# clock10.net
KiCad netlist of a schematic drawn in EAGLE
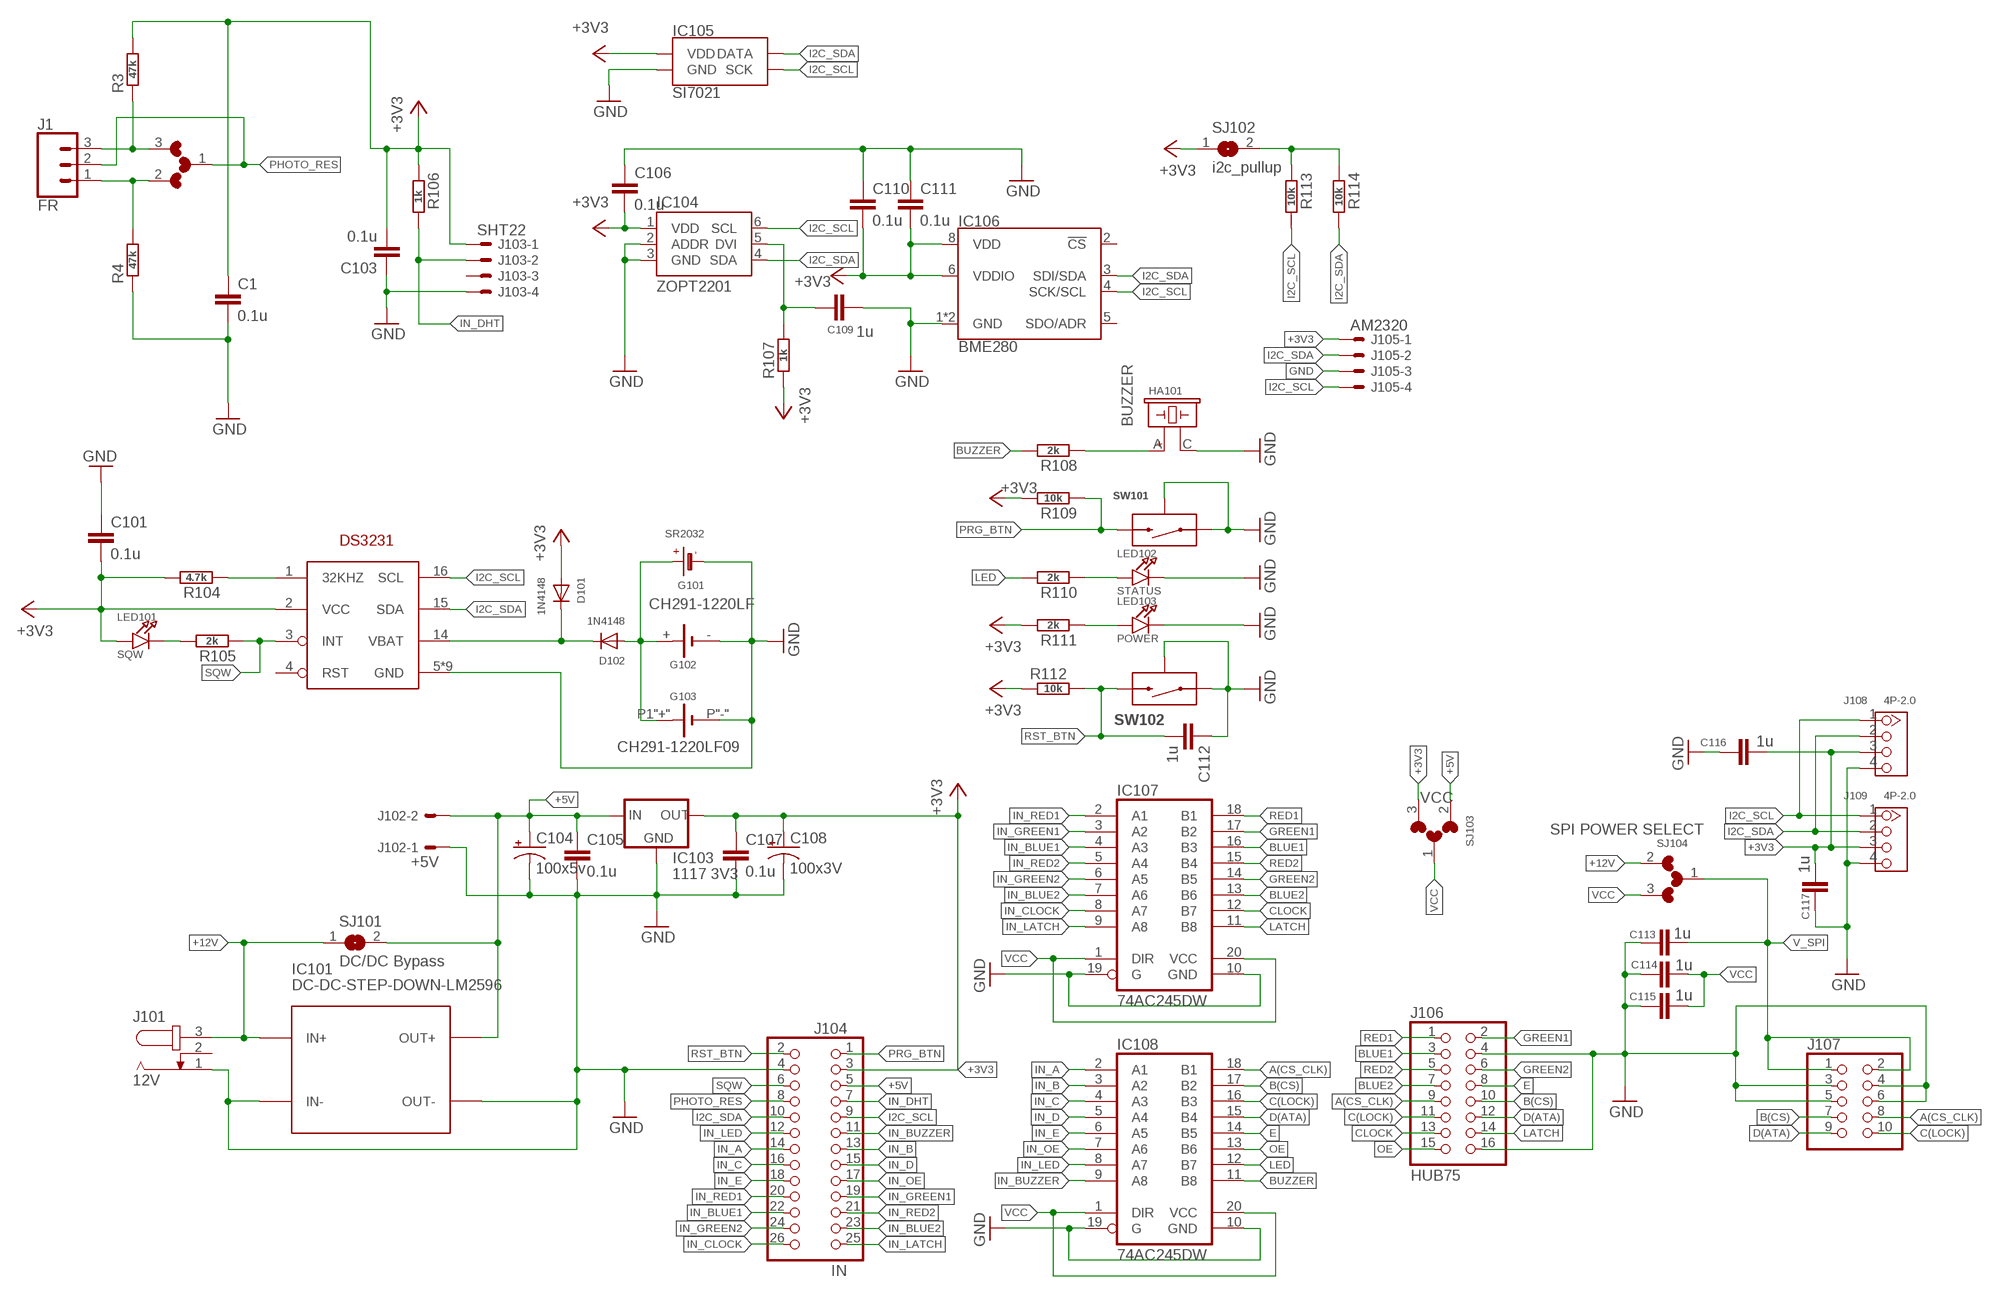
[diagram p0: schematic, sheet 1]
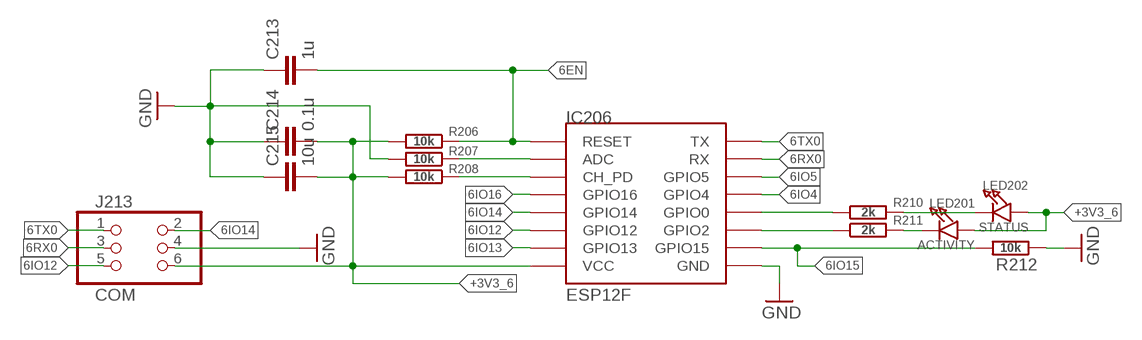
[diagram p1: schematic, sheet 2]

(export (version "E")
  (design (tool "Eeschema 10.0.6"))
  (components
    (comp (ref "C213")
      (value "1u")
      (footprint "eagle-import:0603-CAP")
      (libsource (lib "eagle-import") (part "CAP0603-CAP"))
    )
    (comp (ref "C214")
      (value "0.1u")
      (footprint "eagle-import:0603-CAP")
      (libsource (lib "eagle-import") (part "CAP0603-CAP"))
    )
    (comp (ref "C215")
      (value "10u")
      (footprint "eagle-import:0603-CAP")
      (libsource (lib "eagle-import") (part "CAP0603-CAP"))
    )
    (comp (ref "IC206")
      (value "ESP12F")
      (footprint "eagle-import:ESP12-SMD")
      (libsource (lib "eagle-import") (part "ESP12SMD"))
    )
    (comp (ref "J213")
      (value "COM")
      (footprint "eagle-import:2X03_SMT")
      (libsource (lib "eagle-import") (part "HEADER-2X3SMT"))
    )
    (comp (ref "LED201")
      (value "ACTIVITY")
      (footprint "eagle-import:CHIPLED_0603")
      (libsource (lib "eagle-import") (part "LED0603"))
    )
    (comp (ref "LED202")
      (value "STATUS")
      (footprint "eagle-import:CHIPLED_0603")
      (libsource (lib "eagle-import") (part "LED0603"))
    )
    (comp (ref "R206")
      (value "10k")
      (footprint "eagle-import:R0603")
      (libsource (lib "eagle-import") (part "R-EU_R0603"))
    )
    (comp (ref "R207")
      (value "10k")
      (footprint "eagle-import:R0603")
      (libsource (lib "eagle-import") (part "R-EU_R0603"))
    )
    (comp (ref "R208")
      (value "10k")
      (footprint "eagle-import:R0603")
      (libsource (lib "eagle-import") (part "R-EU_R0603"))
    )
    (comp (ref "R210")
      (value "2k")
      (footprint "eagle-import:R0603")
      (libsource (lib "eagle-import") (part "R-EU_R0603"))
    )
    (comp (ref "R211")
      (value "2k")
      (footprint "eagle-import:R0603")
      (libsource (lib "eagle-import") (part "R-EU_R0603"))
    )
    (comp (ref "R212")
      (value "10k")
      (footprint "eagle-import:R0603")
      (libsource (lib "eagle-import") (part "R-EU_R0603"))
    )
    (comp (ref "C1")
      (value "0.1u")
      (footprint "eagle-import:0603-CAP")
      (libsource (lib "eagle-import") (part "CAP0603-CAP"))
    )
    (comp (ref "C101")
      (value "0.1u")
      (footprint "eagle-import:0603-CAP")
      (libsource (lib "eagle-import") (part "CAP0603-CAP"))
    )
    (comp (ref "C103")
      (value "0.1u")
      (footprint "eagle-import:0603-CAP")
      (libsource (lib "eagle-import") (part "CAP0603-CAP"))
    )
    (comp (ref "C104")
      (value "100x5v")
      (footprint "eagle-import:CPOL-RADIAL-100UF-25V")
      (libsource (lib "eagle-import") (part "CAP_POLPTH1"))
    )
    (comp (ref "C105")
      (value "0.1u")
      (footprint "eagle-import:0603-CAP")
      (libsource (lib "eagle-import") (part "CAP0603-CAP"))
    )
    (comp (ref "C106")
      (value "0.1u")
      (footprint "eagle-import:0603-CAP")
      (libsource (lib "eagle-import") (part "CAP0603-CAP"))
    )
    (comp (ref "C107")
      (value "0.1u")
      (footprint "eagle-import:0603-CAP")
      (libsource (lib "eagle-import") (part "CAP0603-CAP"))
    )
    (comp (ref "C108")
      (value "100x3V")
      (footprint "eagle-import:CPOL-RADIAL-100UF-25V")
      (libsource (lib "eagle-import") (part "CAP_POLPTH1"))
    )
    (comp (ref "C109")
      (value "1u")
      (footprint "eagle-import:0603-CAP")
      (libsource (lib "eagle-import") (part "CAP0603-CAP"))
    )
    (comp (ref "C110")
      (value "0.1u")
      (footprint "eagle-import:0603-CAP")
      (libsource (lib "eagle-import") (part "CAP0603-CAP"))
    )
    (comp (ref "C111")
      (value "0.1u")
      (footprint "eagle-import:0603-CAP")
      (libsource (lib "eagle-import") (part "CAP0603-CAP"))
    )
    (comp (ref "C112")
      (value "1u")
      (footprint "eagle-import:0603-CAP")
      (libsource (lib "eagle-import") (part "CAP0603-CAP"))
    )
    (comp (ref "C113")
      (value "1u")
      (footprint "eagle-import:0603-CAP")
      (libsource (lib "eagle-import") (part "CAP0603-CAP"))
    )
    (comp (ref "C114")
      (value "1u")
      (footprint "eagle-import:0603-CAP")
      (libsource (lib "eagle-import") (part "CAP0603-CAP"))
    )
    (comp (ref "C115")
      (value "1u")
      (footprint "eagle-import:0603-CAP")
      (libsource (lib "eagle-import") (part "CAP0603-CAP"))
    )
    (comp (ref "C116")
      (value "1u")
      (footprint "eagle-import:0603-CAP")
      (libsource (lib "eagle-import") (part "CAP0603-CAP"))
    )
    (comp (ref "C117")
      (value "1u")
      (footprint "eagle-import:0603-CAP")
      (libsource (lib "eagle-import") (part "CAP0603-CAP"))
    )
    (comp (ref "D101")
      (value "1N4148")
      (footprint "eagle-import:SOD-323F")
      (libsource (lib "eagle-import") (part "DIODESOD-323F"))
    )
    (comp (ref "D102")
      (value "1N4148")
      (footprint "eagle-import:SOD-323F")
      (libsource (lib "eagle-import") (part "DIODESOD-323F"))
    )
    (comp (ref "G101")
      (value "SR2032")
      (footprint "eagle-import:CR2032")
      (libsource (lib "eagle-import") (part "BATTERYCR2032"))
    )
    (comp (ref "G102")
      (value "CH291-1220LF")
      (footprint "eagle-import:CH291-1220LF")
      (libsource (lib "eagle-import") (part "CH291-1220LF"))
    )
    (comp (ref "G103")
      (value "CH291-1220LF09")
      (footprint "eagle-import:CH23-09LF")
      (libsource (lib "eagle-import") (part "CH291-1220LF09"))
    )
    (comp (ref "HA101")
      (value "BUZZER")
      (footprint "eagle-import:PBUZ_12X7.5")
      (libsource (lib "eagle-import") (part "PIEZO_BUZZERHYDZ12X7.5"))
    )
    (comp (ref "IC101")
      (value "DC-DC-STEP-DOWN-LM2596")
      (footprint "eagle-import:DC-DC-STEP-DOWN-LM2596")
      (libsource (lib "eagle-import") (part "DC-DC-STEP-DOWN-LM2596"))
    )
    (comp (ref "IC102")
      (value "DS3231W")
      (footprint "eagle-import:SO16W")
      (libsource (lib "eagle-import") (part "DS3231W"))
    )
    (comp (ref "IC103")
      (value "1117 3V3")
      (footprint "eagle-import:SOT223")
      (libsource (lib "eagle-import") (part "V_REG_LD1117VXXSMD"))
    )
    (comp (ref "IC104")
      (value "ZOPT2201")
      (footprint "eagle-import:WSOF6L")
      (libsource (lib "eagle-import") (part "BH1750"))
    )
    (comp (ref "IC105")
      (value "SI7021")
      (footprint "eagle-import:DFN-6-3X3-SI7021")
      (libsource (lib "eagle-import") (part "SI7021"))
    )
    (comp (ref "IC106")
      (value "BME280")
      (footprint "eagle-import:LGA-8-2.5X2.5")
      (libsource (lib "eagle-import") (part "BME280"))
    )
    (comp (ref "IC107")
      (value "74AC245DW")
      (footprint "eagle-import:SO20W")
      (libsource (lib "eagle-import") (part "74245DWAC"))
    )
    (comp (ref "IC108")
      (value "74AC245DW")
      (footprint "eagle-import:SO20W")
      (libsource (lib "eagle-import") (part "74245DWAC"))
    )
    (comp (ref "J1")
      (value "FR")
      (footprint "eagle-import:1X03")
      (libsource (lib "eagle-import") (part "CONN_03"))
    )
    (comp (ref "J101")
      (value "12V")
      (footprint "eagle-import:SPC4077")
      (libsource (lib "eagle-import") (part "JACK-PLUG0"))
    )
    (comp (ref "J102")
      (value "+5V")
      (footprint "eagle-import:70543-02")
      (libsource (lib "eagle-import") (part "C-GRID-02-70543"))
    )
    (comp (ref "J103")
      (value "SHT22")
      (footprint "eagle-import:70543-04")
      (libsource (lib "eagle-import") (part "C-GRID-04-70543"))
    )
    (comp (ref "J104")
      (value "IN")
      (footprint "eagle-import:2X13")
      (libsource (lib "eagle-import") (part "HEADER-2X13"))
    )
    (comp (ref "J105")
      (value "AM2320")
      (footprint "eagle-import:70543-04")
      (libsource (lib "eagle-import") (part "C-GRID-04-70543"))
    )
    (comp (ref "J106")
      (value "HUB75")
      (footprint "eagle-import:2X08")
      (libsource (lib "eagle-import") (part "PINHD-2X8"))
    )
    (comp (ref "J107")
      (value "HEADER-2X5IDC")
      (footprint "eagle-import:2X05_IDC")
      (libsource (lib "eagle-import") (part "HEADER-2X5IDC"))
    )
    (comp (ref "J108")
      (value "4P-2.0")
      (footprint "eagle-import:HW4-2.0")
      (libsource (lib "eagle-import") (part "GROVE-CONNECTOR-DIP(4P-2.0)"))
    )
    (comp (ref "J109")
      (value "4P-2.0")
      (footprint "eagle-import:HW4-2.0")
      (libsource (lib "eagle-import") (part "GROVE-CONNECTOR-DIP(4P-2.0)"))
    )
    (comp (ref "LED101")
      (value "SQW")
      (footprint "eagle-import:CHIPLED_0603")
      (libsource (lib "eagle-import") (part "LED0603"))
    )
    (comp (ref "LED102")
      (value "STATUS")
      (footprint "eagle-import:CHIPLED_0603")
      (libsource (lib "eagle-import") (part "LED0603"))
    )
    (comp (ref "LED103")
      (value "POWER")
      (footprint "eagle-import:CHIPLED_0603")
      (libsource (lib "eagle-import") (part "LED0603"))
    )
    (comp (ref "R3")
      (value "47k")
      (footprint "eagle-import:R0603")
      (libsource (lib "eagle-import") (part "R-EU_R0603"))
    )
    (comp (ref "R4")
      (value "47k")
      (footprint "eagle-import:R0603")
      (libsource (lib "eagle-import") (part "R-EU_R0603"))
    )
    (comp (ref "R104")
      (value "4.7k")
      (footprint "eagle-import:R0603")
      (libsource (lib "eagle-import") (part "R-EU_R0603"))
    )
    (comp (ref "R105")
      (value "2k")
      (footprint "eagle-import:R0603")
      (libsource (lib "eagle-import") (part "R-EU_R0603"))
    )
    (comp (ref "R106")
      (value "1k")
      (footprint "eagle-import:R0603")
      (libsource (lib "eagle-import") (part "R-EU_R0603"))
    )
    (comp (ref "R107")
      (value "1k")
      (footprint "eagle-import:R0603")
      (libsource (lib "eagle-import") (part "R-EU_R0603"))
    )
    (comp (ref "R108")
      (value "2k")
      (footprint "eagle-import:R0603")
      (libsource (lib "eagle-import") (part "R-EU_R0603"))
    )
    (comp (ref "R109")
      (value "10k")
      (footprint "eagle-import:R0603")
      (libsource (lib "eagle-import") (part "R-EU_R0603"))
    )
    (comp (ref "R110")
      (value "2k")
      (footprint "eagle-import:R0603")
      (libsource (lib "eagle-import") (part "R-EU_R0603"))
    )
    (comp (ref "R111")
      (value "2k")
      (footprint "eagle-import:R0603")
      (libsource (lib "eagle-import") (part "R-EU_R0603"))
    )
    (comp (ref "R112")
      (value "10k")
      (footprint "eagle-import:R0603")
      (libsource (lib "eagle-import") (part "R-EU_R0603"))
    )
    (comp (ref "R113")
      (value "10k")
      (footprint "eagle-import:R0603")
      (libsource (lib "eagle-import") (part "R-EU_R0603"))
    )
    (comp (ref "R114")
      (value "10k")
      (footprint "eagle-import:R0603")
      (libsource (lib "eagle-import") (part "R-EU_R0603"))
    )
    (comp (ref "SJ1")
      (value "PR POS/NEG")
      (footprint "eagle-import:MICROBUILDER_SOLDERJUMPER_ARROW_NOPASTE_3")
      (libsource (lib "eagle-import") (part "MICROBUILDER_SOLDERJUMPER3"))
    )
    (comp (ref "SJ101")
      (value "DC/DC Bypass")
      (footprint "eagle-import:MICROBUILDER_SOLDERJUMPER_ARROW_NOPASTE")
      (libsource (lib "eagle-import") (part "MICROBUILDER_SOLDERJUMPER"))
    )
    (comp (ref "SJ102")
      (value "i2c_pullup")
      (footprint "eagle-import:MICROBUILDER_SOLDERJUMPER_ARROW_NOPASTE")
      (libsource (lib "eagle-import") (part "MICROBUILDER_SOLDERJUMPER"))
    )
    (comp (ref "SJ103")
      (value "VCC")
      (footprint "eagle-import:MICROBUILDER_SOLDERJUMPER_ARROW_NOPASTE_3")
      (libsource (lib "eagle-import") (part "MICROBUILDER_SOLDERJUMPER3"))
    )
    (comp (ref "SJ104")
      (value "SPI POWER SELECT")
      (footprint "eagle-import:MICROBUILDER_SOLDERJUMPER_ARROW_NOPASTE_3")
      (libsource (lib "eagle-import") (part "MICROBUILDER_SOLDERJUMPER3"))
    )
    (comp (ref "SW101")
      (value "PRG")
      (footprint "eagle-import:MICROPUSH-BUT_TOP")
      (libsource (lib "eagle-import") (part "MICROSWITCH-BUTTON"))
    )
    (comp (ref "SW102")
      (value "RST")
      (footprint "eagle-import:MICROPUSH-BUT_TOP")
      (libsource (lib "eagle-import") (part "MICROSWITCH-BUTTON"))
    )
  )
  (nets
    (net (code "1") (name "+3V3") (class "Default")
      (node (ref "C1") (pin "1") (pinfunction "1_1") (pintype "passive"))
      (node (ref "C101") (pin "2") (pinfunction "2_2") (pintype "passive"))
      (node (ref "C103") (pin "2") (pinfunction "2_2") (pintype "passive"))
      (node (ref "C106") (pin "2") (pinfunction "2_2") (pintype "passive"))
      (node (ref "C107") (pin "1") (pinfunction "1_1") (pintype "passive"))
      (node (ref "C108") (pin "1") (pinfunction "+_1") (pintype "passive"))
      (node (ref "C110") (pin "2") (pinfunction "2_2") (pintype "passive"))
      (node (ref "C111") (pin "2") (pinfunction "2_2") (pintype "passive"))
      (node (ref "C116") (pin "2") (pinfunction "2_2") (pintype "passive"))
      (node (ref "C117") (pin "2") (pinfunction "2_2") (pintype "passive"))
      (node (ref "D101") (pin "A") (pinfunction "A_A") (pintype "passive"))
      (node (ref "IC102") (pin "2") (pinfunction "VCC_2") (pintype "input"))
      (node (ref "IC103") (pin "2") (pinfunction "OUT_2") (pintype "passive"))
      (node (ref "IC103") (pin "4") (pinfunction "OUT_4") (pintype "passive"))
      (node (ref "IC104") (pin "1") (pinfunction "VDD_1") (pintype "power_in"))
      (node (ref "IC105") (pin "VDD") (pinfunction "VDD_VDD") (pintype "power_in"))
      (node (ref "IC106") (pin "6") (pinfunction "VDDIO_6") (pintype "bidirectional"))
      (node (ref "IC106") (pin "8") (pinfunction "VDD_8") (pintype "bidirectional"))
      (node (ref "J103") (pin "1") (pinfunction "S_1") (pintype "passive"))
      (node (ref "J104") (pin "3") (pinfunction "3_3") (pintype "passive"))
      (node (ref "J105") (pin "1") (pinfunction "S_1") (pintype "passive"))
      (node (ref "J108") (pin "3") (pinfunction "3_3") (pintype "bidirectional"))
      (node (ref "J109") (pin "3") (pinfunction "3_3") (pintype "bidirectional"))
      (node (ref "LED101") (pin "A") (pinfunction "A_A") (pintype "passive"))
      (node (ref "R104") (pin "2") (pinfunction "2_2") (pintype "passive"))
      (node (ref "R106") (pin "1") (pinfunction "1_1") (pintype "passive"))
      (node (ref "R107") (pin "1") (pinfunction "1_1") (pintype "passive"))
      (node (ref "R109") (pin "2") (pinfunction "2_2") (pintype "passive"))
      (node (ref "R111") (pin "2") (pinfunction "2_2") (pintype "passive"))
      (node (ref "R112") (pin "1") (pinfunction "1_1") (pintype "passive"))
      (node (ref "R3") (pin "2") (pinfunction "2_2") (pintype "passive"))
      (node (ref "SJ102") (pin "1") (pinfunction "1_1") (pintype "passive"))
      (node (ref "SJ103") (pin "3") (pinfunction "3_3") (pintype "passive"))
    )
    (net (code "2") (name "+3V3_6") (class "Default")
      (node (ref "C214") (pin "2") (pinfunction "2_2") (pintype "passive"))
      (node (ref "C215") (pin "2") (pinfunction "2_2") (pintype "passive"))
      (node (ref "IC206") (pin "VCC") (pinfunction "VCC_VCC") (pintype "bidirectional"))
      (node (ref "J213") (pin "6") (pinfunction "6_6") (pintype "passive"))
      (node (ref "LED201") (pin "A") (pinfunction "A_A") (pintype "passive"))
      (node (ref "LED202") (pin "A") (pinfunction "A_A") (pintype "passive"))
      (node (ref "R206") (pin "2") (pinfunction "2_2") (pintype "passive"))
      (node (ref "R208") (pin "2") (pinfunction "2_2") (pintype "passive"))
    )
    (net (code "3") (name "+5V") (class "Default")
      (node (ref "C104") (pin "1") (pinfunction "+_1") (pintype "passive"))
      (node (ref "C105") (pin "1") (pinfunction "1_1") (pintype "passive"))
      (node (ref "IC101") (pin "OUT+") (pinfunction "OUT+_OUT+") (pintype "bidirectional"))
      (node (ref "IC103") (pin "3") (pinfunction "IN_3") (pintype "input"))
      (node (ref "J102") (pin "2") (pinfunction "S_2") (pintype "passive"))
      (node (ref "J104") (pin "5") (pinfunction "5_5") (pintype "passive"))
      (node (ref "SJ101") (pin "2") (pinfunction "2_2") (pintype "passive"))
      (node (ref "SJ103") (pin "2") (pinfunction "2_2") (pintype "passive"))
    )
    (net (code "4") (name "+12V") (class "Default")
      (node (ref "IC101") (pin "IN+") (pinfunction "IN+_IN+") (pintype "bidirectional"))
      (node (ref "J101") (pin "3") (pinfunction "3_3") (pintype "passive"))
      (node (ref "SJ101") (pin "1") (pinfunction "1_1") (pintype "passive"))
      (node (ref "SJ104") (pin "2") (pinfunction "2_2") (pintype "passive"))
    )
    (net (code "5") (name "6EN") (class "Default")
      (node (ref "C213") (pin "2") (pinfunction "2_2") (pintype "passive"))
      (node (ref "IC206") (pin "RESET") (pinfunction "RESET_RESET") (pintype "bidirectional"))
      (node (ref "R206") (pin "1") (pinfunction "1_1") (pintype "passive"))
    )
    (net (code "6") (name "6IO4") (class "Default")
      (node (ref "IC206") (pin "GPIO4") (pinfunction "GPIO4_GPIO4") (pintype "bidirectional"))
    )
    (net (code "7") (name "6IO5") (class "Default")
      (node (ref "IC206") (pin "GPIO5") (pinfunction "GPIO5_GPIO5") (pintype "bidirectional"))
    )
    (net (code "8") (name "6IO12") (class "Default")
      (node (ref "IC206") (pin "GPIO12") (pinfunction "GPIO12_GPIO12") (pintype "bidirectional"))
      (node (ref "J213") (pin "5") (pinfunction "5_5") (pintype "passive"))
    )
    (net (code "9") (name "6IO13") (class "Default")
      (node (ref "IC206") (pin "GPIO13") (pinfunction "GPIO13_GPIO13") (pintype "bidirectional"))
    )
    (net (code "10") (name "6IO14") (class "Default")
      (node (ref "IC206") (pin "GPIO14") (pinfunction "GPIO14_GPIO14") (pintype "bidirectional"))
      (node (ref "J213") (pin "2") (pinfunction "2_2") (pintype "passive"))
    )
    (net (code "11") (name "6IO15") (class "Default")
      (node (ref "IC206") (pin "GPIO15") (pinfunction "GPIO15_GPIO15") (pintype "bidirectional"))
      (node (ref "R212") (pin "2") (pinfunction "2_2") (pintype "passive"))
    )
    (net (code "12") (name "6IO16") (class "Default")
      (node (ref "IC206") (pin "GPIO16") (pinfunction "GPIO16_GPIO16") (pintype "bidirectional"))
    )
    (net (code "13") (name "6RX0") (class "Default")
      (node (ref "IC206") (pin "RXD0") (pinfunction "RX_RXD0") (pintype "bidirectional"))
      (node (ref "J213") (pin "3") (pinfunction "3_3") (pintype "passive"))
    )
    (net (code "14") (name "6TX0") (class "Default")
      (node (ref "IC206") (pin "TXD0") (pinfunction "TX_TXD0") (pintype "bidirectional"))
      (node (ref "J213") (pin "1") (pinfunction "1_1") (pintype "passive"))
    )
    (net (code "15") (name "A(CS_CLK)") (class "Default")
      (node (ref "IC108") (pin "18") (pinfunction "B1_18") (pintype "bidirectional"))
      (node (ref "J106") (pin "9") (pinfunction "9_9") (pintype "passive"))
      (node (ref "J107") (pin "8") (pinfunction "8_8") (pintype "passive"))
    )
    (net (code "16") (name "B(CS)") (class "Default")
      (node (ref "IC108") (pin "17") (pinfunction "B2_17") (pintype "bidirectional"))
      (node (ref "J106") (pin "10") (pinfunction "10_10") (pintype "passive"))
      (node (ref "J107") (pin "7") (pinfunction "7_7") (pintype "passive"))
    )
    (net (code "17") (name "BLUE1") (class "Default")
      (node (ref "IC107") (pin "16") (pinfunction "B3_16") (pintype "bidirectional"))
      (node (ref "J106") (pin "3") (pinfunction "3_3") (pintype "passive"))
    )
    (net (code "18") (name "BLUE2") (class "Default")
      (node (ref "IC107") (pin "13") (pinfunction "B6_13") (pintype "bidirectional"))
      (node (ref "J106") (pin "7") (pinfunction "7_7") (pintype "passive"))
    )
    (net (code "19") (name "BUZZER") (class "Default")
      (node (ref "IC108") (pin "11") (pinfunction "B8_11") (pintype "bidirectional"))
      (node (ref "R108") (pin "2") (pinfunction "2_2") (pintype "passive"))
    )
    (net (code "20") (name "C(LOCK)") (class "Default")
      (node (ref "IC108") (pin "16") (pinfunction "B3_16") (pintype "bidirectional"))
      (node (ref "J106") (pin "11") (pinfunction "11_11") (pintype "passive"))
      (node (ref "J107") (pin "10") (pinfunction "10_10") (pintype "passive"))
    )
    (net (code "21") (name "CLOCK") (class "Default")
      (node (ref "IC107") (pin "12") (pinfunction "B7_12") (pintype "bidirectional"))
      (node (ref "J106") (pin "13") (pinfunction "13_13") (pintype "passive"))
    )
    (net (code "22") (name "D(ATA)") (class "Default")
      (node (ref "IC108") (pin "15") (pinfunction "B4_15") (pintype "bidirectional"))
      (node (ref "J106") (pin "12") (pinfunction "12_12") (pintype "passive"))
      (node (ref "J107") (pin "9") (pinfunction "9_9") (pintype "passive"))
    )
    (net (code "23") (name "E") (class "Default")
      (node (ref "IC108") (pin "14") (pinfunction "B5_14") (pintype "bidirectional"))
      (node (ref "J106") (pin "8") (pinfunction "8_8") (pintype "passive"))
    )
    (net (code "24") (name "GND") (class "Default")
      (node (ref "C1") (pin "2") (pinfunction "2_2") (pintype "passive"))
      (node (ref "C101") (pin "1") (pinfunction "1_1") (pintype "passive"))
      (node (ref "C103") (pin "1") (pinfunction "1_1") (pintype "passive"))
      (node (ref "C104") (pin "2") (pinfunction "-_2") (pintype "passive"))
      (node (ref "C105") (pin "2") (pinfunction "2_2") (pintype "passive"))
      (node (ref "C106") (pin "1") (pinfunction "1_1") (pintype "passive"))
      (node (ref "C107") (pin "2") (pinfunction "2_2") (pintype "passive"))
      (node (ref "C108") (pin "2") (pinfunction "-_2") (pintype "passive"))
      (node (ref "C109") (pin "2") (pinfunction "2_2") (pintype "passive"))
      (node (ref "C110") (pin "1") (pinfunction "1_1") (pintype "passive"))
      (node (ref "C111") (pin "1") (pinfunction "1_1") (pintype "passive"))
      (node (ref "C112") (pin "1") (pinfunction "1_1") (pintype "passive"))
      (node (ref "C113") (pin "2") (pinfunction "2_2") (pintype "passive"))
      (node (ref "C114") (pin "2") (pinfunction "2_2") (pintype "passive"))
      (node (ref "C115") (pin "2") (pinfunction "2_2") (pintype "passive"))
      (node (ref "C116") (pin "1") (pinfunction "1_1") (pintype "passive"))
      (node (ref "C117") (pin "1") (pinfunction "1_1") (pintype "passive"))
      (node (ref "C213") (pin "1") (pinfunction "1_1") (pintype "passive"))
      (node (ref "C214") (pin "1") (pinfunction "1_1") (pintype "passive"))
      (node (ref "C215") (pin "1") (pinfunction "1_1") (pintype "passive"))
      (node (ref "G101") (pin "-") (pinfunction "-_-") (pintype "passive"))
      (node (ref "G102") (pin "-") (pinfunction "-_-") (pintype "passive"))
      (node (ref "G103") (pin "P\"-\"") (pinfunction "-_P\"-\"") (pintype "passive"))
      (node (ref "HA101") (pin "C") (pinfunction "C_C") (pintype "passive"))
      (node (ref "IC101") (pin "IN-") (pinfunction "IN-_IN-") (pintype "bidirectional"))
      (node (ref "IC101") (pin "OUT-") (pinfunction "OUT-_OUT-") (pintype "bidirectional"))
      (node (ref "IC102") (pin "10") (pinfunction "GND_10") (pintype "bidirectional"))
      (node (ref "IC102") (pin "11") (pinfunction "GND_11") (pintype "bidirectional"))
      (node (ref "IC102") (pin "12") (pinfunction "GND_12") (pintype "bidirectional"))
      (node (ref "IC102") (pin "13") (pinfunction "GND_13") (pintype "bidirectional"))
      (node (ref "IC102") (pin "5") (pinfunction "GND_5") (pintype "bidirectional"))
      (node (ref "IC102") (pin "6") (pinfunction "GND_6") (pintype "bidirectional"))
      (node (ref "IC102") (pin "7") (pinfunction "GND_7") (pintype "bidirectional"))
      (node (ref "IC102") (pin "8") (pinfunction "GND_8") (pintype "bidirectional"))
      (node (ref "IC102") (pin "9") (pinfunction "GND_9") (pintype "bidirectional"))
      (node (ref "IC103") (pin "1") (pinfunction "GND_1") (pintype "input"))
      (node (ref "IC104") (pin "2") (pinfunction "ADDR_2") (pintype "input"))
      (node (ref "IC104") (pin "3") (pinfunction "GND_3") (pintype "power_in"))
      (node (ref "IC105") (pin "GND") (pinfunction "GND_GND") (pintype "power_in"))
      (node (ref "IC106") (pin "1") (pinfunction "GND_1") (pintype "bidirectional"))
      (node (ref "IC106") (pin "7") (pinfunction "GND_7") (pintype "bidirectional"))
      (node (ref "IC107") (pin "10") (pinfunction "GND_10") (pintype "power_in"))
      (node (ref "IC107") (pin "19") (pinfunction "G_19") (pintype "input"))
      (node (ref "IC108") (pin "10") (pinfunction "GND_10") (pintype "power_in"))
      (node (ref "IC108") (pin "19") (pinfunction "G_19") (pintype "input"))
      (node (ref "IC206") (pin "GND") (pinfunction "GND_GND") (pintype "bidirectional"))
      (node (ref "J101") (pin "1") (pinfunction "1_1") (pintype "passive"))
      (node (ref "J102") (pin "1") (pinfunction "S_1") (pintype "passive"))
      (node (ref "J103") (pin "4") (pinfunction "S_4") (pintype "passive"))
      (node (ref "J104") (pin "4") (pinfunction "4_4") (pintype "passive"))
      (node (ref "J105") (pin "3") (pinfunction "S_3") (pintype "passive"))
      (node (ref "J106") (pin "16") (pinfunction "16_16") (pintype "passive"))
      (node (ref "J106") (pin "4") (pinfunction "4_4") (pintype "passive"))
      (node (ref "J107") (pin "3") (pinfunction "3_3") (pintype "passive"))
      (node (ref "J107") (pin "4") (pinfunction "4_4") (pintype "passive"))
      (node (ref "J107") (pin "5") (pinfunction "5_5") (pintype "passive"))
      (node (ref "J107") (pin "6") (pinfunction "6_6") (pintype "passive"))
      (node (ref "J108") (pin "4") (pinfunction "4_4") (pintype "bidirectional"))
      (node (ref "J109") (pin "4") (pinfunction "4_4") (pintype "bidirectional"))
      (node (ref "J213") (pin "4") (pinfunction "4_4") (pintype "passive"))
      (node (ref "LED102") (pin "C") (pinfunction "C_C") (pintype "passive"))
      (node (ref "LED103") (pin "C") (pinfunction "C_C") (pintype "passive"))
      (node (ref "R207") (pin "2") (pinfunction "2_2") (pintype "passive"))
      (node (ref "R212") (pin "1") (pinfunction "1_1") (pintype "passive"))
      (node (ref "R4") (pin "1") (pinfunction "1_1") (pintype "passive"))
      (node (ref "SW101") (pin "A") (pinfunction "A_A") (pintype "passive"))
      (node (ref "SW101") (pin "SH0") (pinfunction "SH_SH0") (pintype "power_in"))
      (node (ref "SW102") (pin "A") (pinfunction "A_A") (pintype "passive"))
      (node (ref "SW102") (pin "SH0") (pinfunction "SH_SH0") (pintype "power_in"))
    )
    (net (code "25") (name "GREEN1") (class "Default")
      (node (ref "IC107") (pin "17") (pinfunction "B2_17") (pintype "bidirectional"))
      (node (ref "J106") (pin "2") (pinfunction "2_2") (pintype "passive"))
    )
    (net (code "26") (name "GREEN2") (class "Default")
      (node (ref "IC107") (pin "14") (pinfunction "B5_14") (pintype "bidirectional"))
      (node (ref "J106") (pin "6") (pinfunction "6_6") (pintype "passive"))
    )
    (net (code "27") (name "I2C_SCL") (class "Default")
      (node (ref "IC102") (pin "16") (pinfunction "SCL_16") (pintype "bidirectional"))
      (node (ref "IC104") (pin "6") (pinfunction "SCL_6") (pintype "bidirectional"))
      (node (ref "IC105") (pin "SCK") (pinfunction "SCK_SCK") (pintype "input"))
      (node (ref "IC106") (pin "4") (pinfunction "SCK/SCL_4") (pintype "bidirectional"))
      (node (ref "J104") (pin "9") (pinfunction "9_9") (pintype "passive"))
      (node (ref "J105") (pin "4") (pinfunction "S_4") (pintype "passive"))
      (node (ref "J108") (pin "1") (pinfunction "1_1") (pintype "bidirectional"))
      (node (ref "J109") (pin "1") (pinfunction "1_1") (pintype "bidirectional"))
      (node (ref "R113") (pin "2") (pinfunction "2_2") (pintype "passive"))
    )
    (net (code "28") (name "I2C_SDA") (class "Default")
      (node (ref "IC102") (pin "15") (pinfunction "SDA_15") (pintype "bidirectional"))
      (node (ref "IC104") (pin "4") (pinfunction "SDA_4") (pintype "bidirectional"))
      (node (ref "IC105") (pin "DATA") (pinfunction "DATA_DATA") (pintype "bidirectional"))
      (node (ref "IC106") (pin "3") (pinfunction "SDI/SDA_3") (pintype "bidirectional"))
      (node (ref "J104") (pin "10") (pinfunction "10_10") (pintype "passive"))
      (node (ref "J105") (pin "2") (pinfunction "S_2") (pintype "passive"))
      (node (ref "J108") (pin "2") (pinfunction "2_2") (pintype "bidirectional"))
      (node (ref "J109") (pin "2") (pinfunction "2_2") (pintype "bidirectional"))
      (node (ref "R114") (pin "2") (pinfunction "2_2") (pintype "passive"))
    )
    (net (code "29") (name "IN_A") (class "Default")
      (node (ref "IC108") (pin "2") (pinfunction "A1_2") (pintype "bidirectional"))
      (node (ref "J104") (pin "14") (pinfunction "14_14") (pintype "passive"))
    )
    (net (code "30") (name "IN_B") (class "Default")
      (node (ref "IC108") (pin "3") (pinfunction "A2_3") (pintype "bidirectional"))
      (node (ref "J104") (pin "13") (pinfunction "13_13") (pintype "passive"))
    )
    (net (code "31") (name "IN_BLUE1") (class "Default")
      (node (ref "IC107") (pin "4") (pinfunction "A3_4") (pintype "bidirectional"))
      (node (ref "J104") (pin "22") (pinfunction "22_22") (pintype "passive"))
    )
    (net (code "32") (name "IN_BLUE2") (class "Default")
      (node (ref "IC107") (pin "7") (pinfunction "A6_7") (pintype "bidirectional"))
      (node (ref "J104") (pin "23") (pinfunction "23_23") (pintype "passive"))
    )
    (net (code "33") (name "IN_BUZZER") (class "Default")
      (node (ref "IC108") (pin "9") (pinfunction "A8_9") (pintype "bidirectional"))
      (node (ref "J104") (pin "11") (pinfunction "11_11") (pintype "passive"))
    )
    (net (code "34") (name "IN_C") (class "Default")
      (node (ref "IC108") (pin "4") (pinfunction "A3_4") (pintype "bidirectional"))
      (node (ref "J104") (pin "16") (pinfunction "16_16") (pintype "passive"))
    )
    (net (code "35") (name "IN_CLOCK") (class "Default")
      (node (ref "IC107") (pin "8") (pinfunction "A7_8") (pintype "bidirectional"))
      (node (ref "J104") (pin "26") (pinfunction "26_26") (pintype "passive"))
    )
    (net (code "36") (name "IN_D") (class "Default")
      (node (ref "IC108") (pin "5") (pinfunction "A4_5") (pintype "bidirectional"))
      (node (ref "J104") (pin "15") (pinfunction "15_15") (pintype "passive"))
    )
    (net (code "37") (name "IN_DHT") (class "Default")
      (node (ref "J103") (pin "2") (pinfunction "S_2") (pintype "passive"))
      (node (ref "J104") (pin "7") (pinfunction "7_7") (pintype "passive"))
      (node (ref "R106") (pin "2") (pinfunction "2_2") (pintype "passive"))
    )
    (net (code "38") (name "IN_E") (class "Default")
      (node (ref "IC108") (pin "6") (pinfunction "A5_6") (pintype "bidirectional"))
      (node (ref "J104") (pin "18") (pinfunction "18_18") (pintype "passive"))
    )
    (net (code "39") (name "IN_GREEN1") (class "Default")
      (node (ref "IC107") (pin "3") (pinfunction "A2_3") (pintype "bidirectional"))
      (node (ref "J104") (pin "19") (pinfunction "19_19") (pintype "passive"))
    )
    (net (code "40") (name "IN_GREEN2") (class "Default")
      (node (ref "IC107") (pin "6") (pinfunction "A5_6") (pintype "bidirectional"))
      (node (ref "J104") (pin "24") (pinfunction "24_24") (pintype "passive"))
    )
    (net (code "41") (name "IN_LATCH") (class "Default")
      (node (ref "IC107") (pin "9") (pinfunction "A8_9") (pintype "bidirectional"))
      (node (ref "J104") (pin "25") (pinfunction "25_25") (pintype "passive"))
    )
    (net (code "42") (name "IN_LED") (class "Default")
      (node (ref "IC108") (pin "8") (pinfunction "A7_8") (pintype "bidirectional"))
      (node (ref "J104") (pin "12") (pinfunction "12_12") (pintype "passive"))
    )
    (net (code "43") (name "IN_OE") (class "Default")
      (node (ref "IC108") (pin "7") (pinfunction "A6_7") (pintype "bidirectional"))
      (node (ref "J104") (pin "17") (pinfunction "17_17") (pintype "passive"))
    )
    (net (code "44") (name "IN_RED1") (class "Default")
      (node (ref "IC107") (pin "2") (pinfunction "A1_2") (pintype "bidirectional"))
      (node (ref "J104") (pin "20") (pinfunction "20_20") (pintype "passive"))
    )
    (net (code "45") (name "IN_RED2") (class "Default")
      (node (ref "IC107") (pin "5") (pinfunction "A4_5") (pintype "bidirectional"))
      (node (ref "J104") (pin "21") (pinfunction "21_21") (pintype "passive"))
    )
    (net (code "46") (name "LATCH") (class "Default")
      (node (ref "IC107") (pin "11") (pinfunction "B8_11") (pintype "bidirectional"))
      (node (ref "J106") (pin "14") (pinfunction "14_14") (pintype "passive"))
    )
    (net (code "47") (name "LED") (class "Default")
      (node (ref "IC108") (pin "12") (pinfunction "B7_12") (pintype "bidirectional"))
      (node (ref "R110") (pin "2") (pinfunction "2_2") (pintype "passive"))
    )
    (net (code "48") (name "Net-(G103-+)") (class "Default")
      (node (ref "D102") (pin "A") (pinfunction "A_A") (pintype "passive"))
      (node (ref "G101") (pin "+") (pinfunction "+_+") (pintype "passive"))
      (node (ref "G102") (pin "+") (pinfunction "+_+") (pintype "passive"))
      (node (ref "G103") (pin "P1\"+\"") (pinfunction "+_P1\"+\"") (pintype "passive"))
    )
    (net (code "49") (name "Net-(HA101-PadA)") (class "Default")
      (node (ref "HA101") (pin "A") (pinfunction "A_A") (pintype "passive"))
      (node (ref "R108") (pin "1") (pinfunction "1_1") (pintype "passive"))
    )
    (net (code "50") (name "Net-(IC102-32KHZ)") (class "Default")
      (node (ref "IC102") (pin "1") (pinfunction "32KHZ_1") (pintype "output"))
      (node (ref "R104") (pin "1") (pinfunction "1_1") (pintype "passive"))
    )
    (net (code "51") (name "Net-(IC102-VBAT)") (class "Default")
      (node (ref "D101") (pin "C") (pinfunction "C_C") (pintype "passive"))
      (node (ref "D102") (pin "C") (pinfunction "C_C") (pintype "passive"))
      (node (ref "IC102") (pin "14") (pinfunction "VBAT_14") (pintype "bidirectional"))
    )
    (net (code "52") (name "Net-(IC104-DVI)") (class "Default")
      (node (ref "C109") (pin "1") (pinfunction "1_1") (pintype "passive"))
      (node (ref "IC104") (pin "5") (pinfunction "DVI_5") (pintype "bidirectional"))
      (node (ref "R107") (pin "2") (pinfunction "2_2") (pintype "passive"))
    )
    (net (code "53") (name "Net-(IC206-PadADC)") (class "Default")
      (node (ref "IC206") (pin "ADC") (pinfunction "ADC_ADC") (pintype "bidirectional"))
      (node (ref "R207") (pin "1") (pinfunction "1_1") (pintype "passive"))
    )
    (net (code "54") (name "Net-(IC206-PadCH_PD)") (class "Default")
      (node (ref "IC206") (pin "CH_PD") (pinfunction "CH_PD_CH_PD") (pintype "bidirectional"))
      (node (ref "R208") (pin "1") (pinfunction "1_1") (pintype "passive"))
    )
    (net (code "55") (name "Net-(IC206-PadGPIO0)") (class "Default")
      (node (ref "IC206") (pin "GPIO0") (pinfunction "GPIO0_GPIO0") (pintype "bidirectional"))
      (node (ref "R210") (pin "1") (pinfunction "1_1") (pintype "passive"))
    )
    (net (code "56") (name "Net-(IC206-PadGPIO2)") (class "Default")
      (node (ref "IC206") (pin "GPIO2") (pinfunction "GPIO2_GPIO2") (pintype "bidirectional"))
      (node (ref "R211") (pin "1") (pinfunction "1_1") (pintype "passive"))
    )
    (net (code "57") (name "Net-(J1-Pad1)") (class "Default")
      (node (ref "J1") (pin "1") (pinfunction "1_1") (pintype "passive"))
      (node (ref "R4") (pin "2") (pinfunction "2_2") (pintype "passive"))
      (node (ref "SJ1") (pin "2") (pinfunction "2_2") (pintype "passive"))
    )
    (net (code "58") (name "Net-(J1-Pad3)") (class "Default")
      (node (ref "J1") (pin "3") (pinfunction "3_3") (pintype "passive"))
      (node (ref "R3") (pin "1") (pinfunction "1_1") (pintype "passive"))
      (node (ref "SJ1") (pin "3") (pinfunction "3_3") (pintype "passive"))
    )
    (net (code "59") (name "Net-(LED101-PadC)") (class "Default")
      (node (ref "LED101") (pin "C") (pinfunction "C_C") (pintype "passive"))
      (node (ref "R105") (pin "2") (pinfunction "2_2") (pintype "passive"))
    )
    (net (code "60") (name "Net-(LED102-PadA)") (class "Default")
      (node (ref "LED102") (pin "A") (pinfunction "A_A") (pintype "passive"))
      (node (ref "R110") (pin "1") (pinfunction "1_1") (pintype "passive"))
    )
    (net (code "61") (name "Net-(LED103-PadA)") (class "Default")
      (node (ref "LED103") (pin "A") (pinfunction "A_A") (pintype "passive"))
      (node (ref "R111") (pin "1") (pinfunction "1_1") (pintype "passive"))
    )
    (net (code "62") (name "Net-(LED201-PadC)") (class "Default")
      (node (ref "LED201") (pin "C") (pinfunction "C_C") (pintype "passive"))
      (node (ref "R211") (pin "2") (pinfunction "2_2") (pintype "passive"))
    )
    (net (code "63") (name "Net-(LED202-PadC)") (class "Default")
      (node (ref "LED202") (pin "C") (pinfunction "C_C") (pintype "passive"))
      (node (ref "R210") (pin "2") (pinfunction "2_2") (pintype "passive"))
    )
    (net (code "64") (name "Net-(R113-Pad1)") (class "Default")
      (node (ref "R113") (pin "1") (pinfunction "1_1") (pintype "passive"))
      (node (ref "R114") (pin "1") (pinfunction "1_1") (pintype "passive"))
      (node (ref "SJ102") (pin "2") (pinfunction "2_2") (pintype "passive"))
    )
    (net (code "65") (name "OE") (class "Default")
      (node (ref "IC108") (pin "13") (pinfunction "B6_13") (pintype "bidirectional"))
      (node (ref "J106") (pin "15") (pinfunction "15_15") (pintype "passive"))
    )
    (net (code "66") (name "PHOTO_RES") (class "Default")
      (node (ref "J1") (pin "2") (pinfunction "2_2") (pintype "passive"))
      (node (ref "J104") (pin "8") (pinfunction "8_8") (pintype "passive"))
      (node (ref "SJ1") (pin "1") (pinfunction "1_1") (pintype "passive"))
    )
    (net (code "67") (name "PRG_BTN") (class "Default")
      (node (ref "J104") (pin "1") (pinfunction "1_1") (pintype "passive"))
      (node (ref "R109") (pin "1") (pinfunction "1_1") (pintype "passive"))
      (node (ref "SW101") (pin "B") (pinfunction "B_B") (pintype "passive"))
    )
    (net (code "68") (name "RED1") (class "Default")
      (node (ref "IC107") (pin "18") (pinfunction "B1_18") (pintype "bidirectional"))
      (node (ref "J106") (pin "1") (pinfunction "1_1") (pintype "passive"))
    )
    (net (code "69") (name "RED2") (class "Default")
      (node (ref "IC107") (pin "15") (pinfunction "B4_15") (pintype "bidirectional"))
      (node (ref "J106") (pin "5") (pinfunction "5_5") (pintype "passive"))
    )
    (net (code "70") (name "RST_BTN") (class "Default")
      (node (ref "C112") (pin "2") (pinfunction "2_2") (pintype "passive"))
      (node (ref "J104") (pin "2") (pinfunction "2_2") (pintype "passive"))
      (node (ref "R112") (pin "2") (pinfunction "2_2") (pintype "passive"))
      (node (ref "SW102") (pin "B") (pinfunction "B_B") (pintype "passive"))
    )
    (net (code "71") (name "SQW") (class "Default")
      (node (ref "IC102") (pin "3") (pinfunction "INT_3") (pintype "bidirectional"))
      (node (ref "J104") (pin "6") (pinfunction "6_6") (pintype "passive"))
      (node (ref "R105") (pin "1") (pinfunction "1_1") (pintype "passive"))
    )
    (net (code "72") (name "VCC") (class "Default")
      (node (ref "C114") (pin "1") (pinfunction "1_1") (pintype "passive"))
      (node (ref "C115") (pin "1") (pinfunction "1_1") (pintype "passive"))
      (node (ref "IC107") (pin "1") (pinfunction "DIR_1") (pintype "input"))
      (node (ref "IC107") (pin "20") (pinfunction "VCC_20") (pintype "power_in"))
      (node (ref "IC108") (pin "1") (pinfunction "DIR_1") (pintype "input"))
      (node (ref "IC108") (pin "20") (pinfunction "VCC_20") (pintype "power_in"))
      (node (ref "SJ103") (pin "1") (pinfunction "1_1") (pintype "passive"))
      (node (ref "SJ104") (pin "3") (pinfunction "3_3") (pintype "passive"))
    )
    (net (code "73") (name "V_SPI") (class "Default")
      (node (ref "C113") (pin "1") (pinfunction "1_1") (pintype "passive"))
      (node (ref "J107") (pin "1") (pinfunction "1_1") (pintype "passive"))
      (node (ref "J107") (pin "2") (pinfunction "2_2") (pintype "passive"))
      (node (ref "SJ104") (pin "1") (pinfunction "1_1") (pintype "passive"))
    )
    (net (code "74") (name "unconnected-(IC102-RST-Pad4)") (class "Default")
      (node (ref "IC102") (pin "4") (pinfunction "RST_4") (pintype "bidirectional"))
    )
    (net (code "75") (name "unconnected-(IC106-SDO{slash}ADR-Pad5)") (class "Default")
      (node (ref "IC106") (pin "5") (pinfunction "SDO/ADR_5") (pintype "bidirectional"))
    )
    (net (code "76") (name "unconnected-(IC106-~{CS}-Pad2)") (class "Default")
      (node (ref "IC106") (pin "2") (pinfunction "~{CS}_2") (pintype "bidirectional"))
    )
    (net (code "77") (name "unconnected-(J101-Pad2)") (class "Default")
      (node (ref "J101") (pin "2") (pinfunction "2_2") (pintype "passive"))
    )
    (net (code "78") (name "unconnected-(J103C-S-Pad3)") (class "Default")
      (node (ref "J103") (pin "3") (pinfunction "S_3") (pintype "passive"))
    )
  )
)
